# Teensy_Board.net
KiCad netlist of a schematic drawn in EAGLE
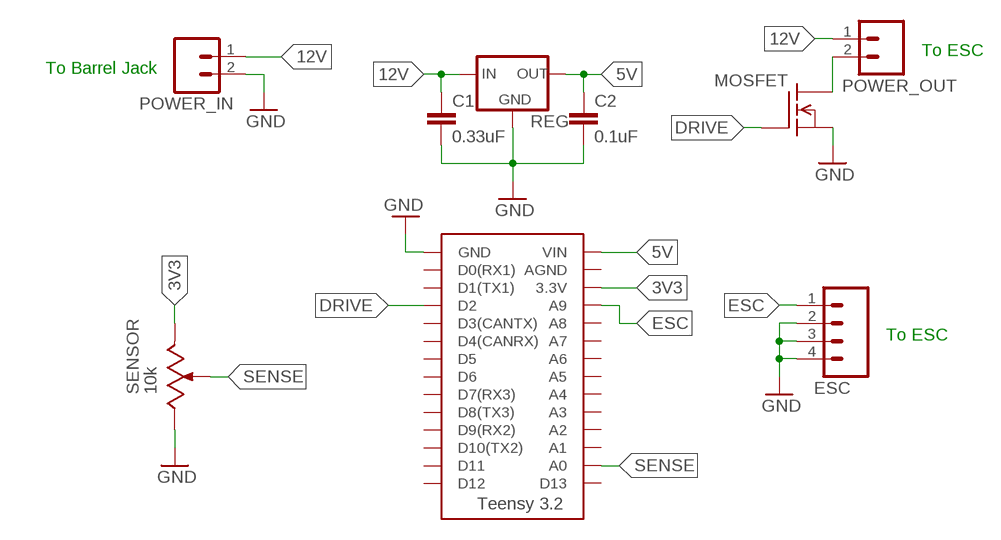
[diagram p0: schematic, sheet 1]

(export (version "E")
  (design (tool "Eeschema 10.0.6"))
  (components
    (comp (ref "C1")
      (value "0.33uF")
      (footprint "eagle-import:0805")
      (libsource (lib "eagle-import") (part "CAP0805"))
    )
    (comp (ref "C2")
      (value "0.1uF")
      (footprint "eagle-import:0805")
      (libsource (lib "eagle-import") (part "CAP0805"))
    )
    (comp (ref "ESC")
      (value "M04")
      (footprint "eagle-import:1X04")
      (libsource (lib "eagle-import") (part "M04"))
    )
    (comp (ref "MOSFET")
      (value "SI2312")
      (footprint "eagle-import:SOT-23")
      (libsource (lib "eagle-import") (part "SI2312"))
    )
    (comp (ref "POWER_IN")
      (value "M02")
      (footprint "eagle-import:1X02")
      (libsource (lib "eagle-import") (part "M02"))
    )
    (comp (ref "POWER_OUT")
      (value "M02")
      (footprint "eagle-import:1X02")
      (libsource (lib "eagle-import") (part "M02"))
    )
    (comp (ref "REG")
      (value "L78L")
      (footprint "eagle-import:SOT-89")
      (libsource (lib "eagle-import") (part "L78L"))
    )
    (comp (ref "SENSOR")
      (value "10k")
      (footprint "eagle-import:SV03A")
      (libsource (lib "eagle-import") (part "SV03"))
    )
    (comp (ref "U$2")
      (value "TEENSY_3.2_SIMPLE")
      (footprint "eagle-import:TEENSY_3.2_SIMPLE")
      (libsource (lib "eagle-import") (part "TEENSY_3.2_SIMPLE"))
    )
  )
  (nets
    (net (code "1") (name "3V3") (class "Default")
      (node (ref "SENSOR") (pin "1") (pinfunction "E_1") (pintype "passive"))
      (node (ref "U$2") (pin "3.3V") (pinfunction "3.3V_3.3V") (pintype "bidirectional"))
    )
    (net (code "2") (name "5V") (class "Default")
      (node (ref "C2") (pin "1") (pinfunction "1_1") (pintype "passive"))
      (node (ref "REG") (pin "1") (pinfunction "OUT_1") (pintype "output"))
      (node (ref "U$2") (pin "VIN") (pinfunction "VIN_VIN") (pintype "bidirectional"))
    )
    (net (code "3") (name "12V") (class "Default")
      (node (ref "C1") (pin "1") (pinfunction "1_1") (pintype "passive"))
      (node (ref "POWER_IN") (pin "1") (pinfunction "1_1") (pintype "passive"))
      (node (ref "POWER_OUT") (pin "1") (pinfunction "1_1") (pintype "passive"))
      (node (ref "REG") (pin "3") (pinfunction "IN_3") (pintype "input"))
    )
    (net (code "4") (name "DRIVE") (class "Default")
      (node (ref "MOSFET") (pin "1") (pinfunction "G_1") (pintype "passive"))
      (node (ref "U$2") (pin "D2") (pinfunction "D2_D2") (pintype "bidirectional"))
    )
    (net (code "5") (name "ESC") (class "Default")
      (node (ref "ESC") (pin "1") (pinfunction "1_1") (pintype "passive"))
      (node (ref "U$2") (pin "A9") (pinfunction "A9_A9") (pintype "bidirectional"))
    )
    (net (code "6") (name "GND") (class "Default")
      (node (ref "C1") (pin "2") (pinfunction "2_2") (pintype "passive"))
      (node (ref "C2") (pin "2") (pinfunction "2_2") (pintype "passive"))
      (node (ref "ESC") (pin "2") (pinfunction "2_2") (pintype "passive"))
      (node (ref "ESC") (pin "3") (pinfunction "3_3") (pintype "passive"))
      (node (ref "ESC") (pin "4") (pinfunction "4_4") (pintype "passive"))
      (node (ref "MOSFET") (pin "2") (pinfunction "S_2") (pintype "passive"))
      (node (ref "POWER_IN") (pin "2") (pinfunction "2_2") (pintype "passive"))
      (node (ref "REG") (pin "2") (pinfunction "GND_2") (pintype "input"))
      (node (ref "REG") (pin "2.1") (pinfunction "GND_2.1") (pintype "input"))
      (node (ref "REG") (pin "2.2") (pinfunction "GND_2.2") (pintype "input"))
      (node (ref "SENSOR") (pin "3") (pinfunction "A_3") (pintype "passive"))
      (node (ref "U$2") (pin "GND") (pinfunction "GND_GND") (pintype "bidirectional"))
    )
    (net (code "7") (name "Net-(MOSFET-D)") (class "Default")
      (node (ref "MOSFET") (pin "3") (pinfunction "D_3") (pintype "passive"))
      (node (ref "POWER_OUT") (pin "2") (pinfunction "2_2") (pintype "passive"))
    )
    (net (code "8") (name "SENSE") (class "Default")
      (node (ref "SENSOR") (pin "2") (pinfunction "S_2") (pintype "passive"))
      (node (ref "SENSOR") (pin "2.1") (pinfunction "S_2.1") (pintype "passive"))
      (node (ref "U$2") (pin "A0") (pinfunction "A0_A0") (pintype "bidirectional"))
    )
    (net (code "9") (name "unconnected-(U$2-PadA1)") (class "Default")
      (node (ref "U$2") (pin "A1") (pinfunction "A1_A1") (pintype "bidirectional"))
    )
    (net (code "10") (name "unconnected-(U$2-PadA2)") (class "Default")
      (node (ref "U$2") (pin "A2") (pinfunction "A2_A2") (pintype "bidirectional"))
    )
    (net (code "11") (name "unconnected-(U$2-PadA3)") (class "Default")
      (node (ref "U$2") (pin "A3") (pinfunction "A3_A3") (pintype "bidirectional"))
    )
    (net (code "12") (name "unconnected-(U$2-PadA4)") (class "Default")
      (node (ref "U$2") (pin "A4") (pinfunction "A4_A4") (pintype "bidirectional"))
    )
    (net (code "13") (name "unconnected-(U$2-PadA5)") (class "Default")
      (node (ref "U$2") (pin "A5") (pinfunction "A5_A5") (pintype "bidirectional"))
    )
    (net (code "14") (name "unconnected-(U$2-PadA6)") (class "Default")
      (node (ref "U$2") (pin "A6") (pinfunction "A6_A6") (pintype "bidirectional"))
    )
    (net (code "15") (name "unconnected-(U$2-PadA7)") (class "Default")
      (node (ref "U$2") (pin "A7") (pinfunction "A7_A7") (pintype "bidirectional"))
    )
    (net (code "16") (name "unconnected-(U$2-PadA8)") (class "Default")
      (node (ref "U$2") (pin "A8") (pinfunction "A8_A8") (pintype "bidirectional"))
    )
    (net (code "17") (name "unconnected-(U$2-PadAGND)") (class "Default")
      (node (ref "U$2") (pin "AGND") (pinfunction "AGND_AGND") (pintype "bidirectional"))
    )
    (net (code "18") (name "unconnected-(U$2-PadD0(RX1))") (class "Default")
      (node (ref "U$2") (pin "D0(RX1)") (pinfunction "D0(RX1)_D0(RX1)") (pintype "bidirectional"))
    )
    (net (code "19") (name "unconnected-(U$2-PadD1(TX1))") (class "Default")
      (node (ref "U$2") (pin "D1(TX1)") (pinfunction "D1(TX1)_D1(TX1)") (pintype "bidirectional"))
    )
    (net (code "20") (name "unconnected-(U$2-PadD3(CANTX))") (class "Default")
      (node (ref "U$2") (pin "D3(CANTX)") (pinfunction "D3(CANTX)_D3(CANTX)") (pintype "bidirectional"))
    )
    (net (code "21") (name "unconnected-(U$2-PadD4(CANRX))") (class "Default")
      (node (ref "U$2") (pin "D4(CANRX)") (pinfunction "D4(CANRX)_D4(CANRX)") (pintype "bidirectional"))
    )
    (net (code "22") (name "unconnected-(U$2-PadD5)") (class "Default")
      (node (ref "U$2") (pin "D5") (pinfunction "D5_D5") (pintype "bidirectional"))
    )
    (net (code "23") (name "unconnected-(U$2-PadD6)") (class "Default")
      (node (ref "U$2") (pin "D6") (pinfunction "D6_D6") (pintype "bidirectional"))
    )
    (net (code "24") (name "unconnected-(U$2-PadD7(RX3))") (class "Default")
      (node (ref "U$2") (pin "D7(RX3)") (pinfunction "D7(RX3)_D7(RX3)") (pintype "bidirectional"))
    )
    (net (code "25") (name "unconnected-(U$2-PadD8(TX3))") (class "Default")
      (node (ref "U$2") (pin "D8(TX3)") (pinfunction "D8(TX3)_D8(TX3)") (pintype "bidirectional"))
    )
    (net (code "26") (name "unconnected-(U$2-PadD9(RX2))") (class "Default")
      (node (ref "U$2") (pin "D9(RX2)") (pinfunction "D9(RX2)_D9(RX2)") (pintype "bidirectional"))
    )
    (net (code "27") (name "unconnected-(U$2-PadD10(TX2))") (class "Default")
      (node (ref "U$2") (pin "D10(TX2)") (pinfunction "D10(TX2)_D10(TX2)") (pintype "bidirectional"))
    )
    (net (code "28") (name "unconnected-(U$2-PadD11)") (class "Default")
      (node (ref "U$2") (pin "D11") (pinfunction "D11_D11") (pintype "bidirectional"))
    )
    (net (code "29") (name "unconnected-(U$2-PadD12)") (class "Default")
      (node (ref "U$2") (pin "D12") (pinfunction "D12_D12") (pintype "bidirectional"))
    )
    (net (code "30") (name "unconnected-(U$2-PadD13)") (class "Default")
      (node (ref "U$2") (pin "D13") (pinfunction "D13_D13") (pintype "bidirectional"))
    )
  )
)
